# Extension.net
KiCad netlist of a schematic drawn in Altium Designer
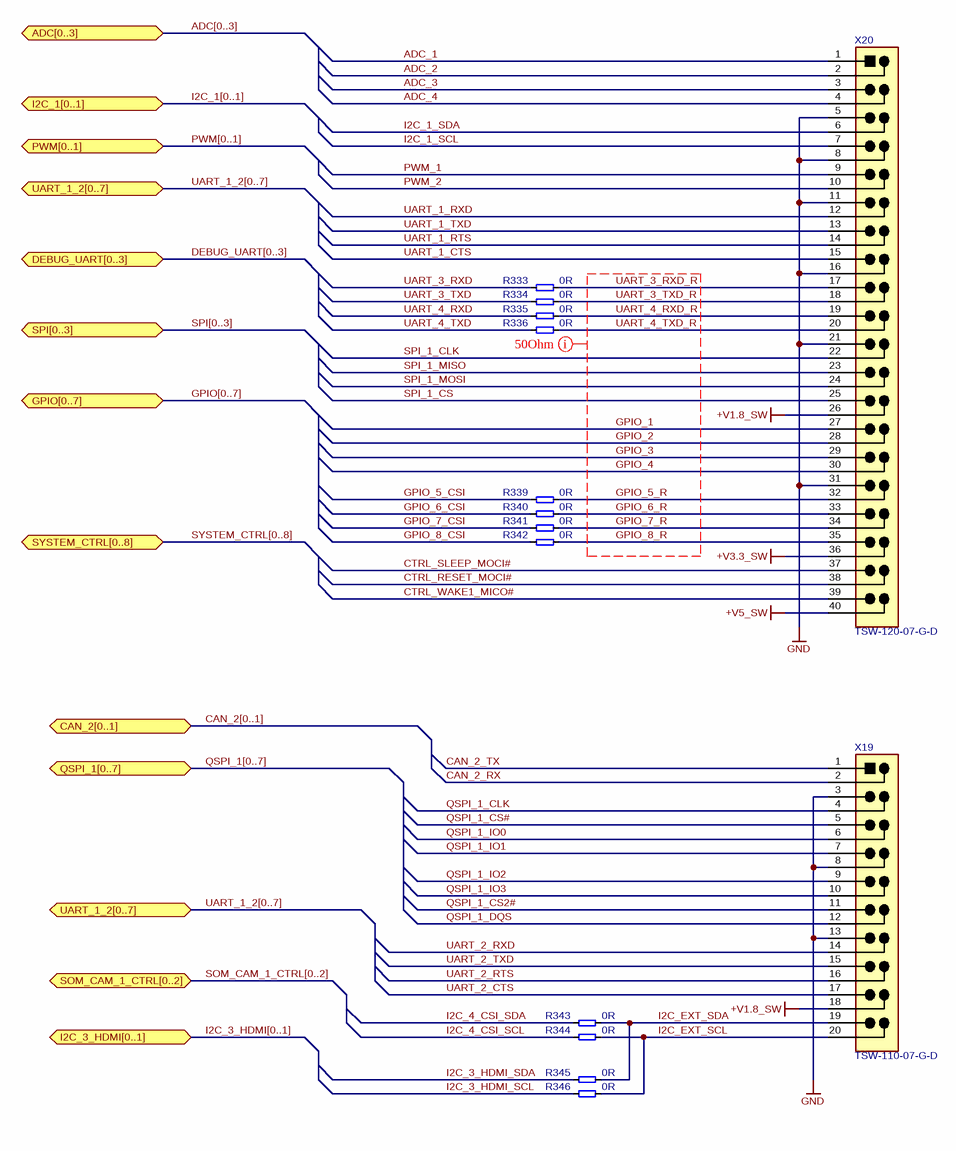
[diagram p0: Extension.SchDoc]

(export (version "E")
  (design (tool "Eeschema 10.0.6"))
  (components
    (comp (ref "R333")
      (value "0R")
      (footprint "T_RESC0603X30N")
      (description "Resistor 0 ohm 63mW 1% 0603")
      (fields (field (name "TOLERANCE") "1%"))
      (libsource (lib "Dahlia Carrier Board") (part "R-0R-63mW-1%-0603"))
    )
    (comp (ref "R334")
      (value "0R")
      (footprint "T_RESC0603X30N")
      (description "Resistor 0 ohm 63mW 1% 0603")
      (fields (field (name "TOLERANCE") "1%"))
      (libsource (lib "Dahlia Carrier Board") (part "R-0R-63mW-1%-0603"))
    )
    (comp (ref "R335")
      (value "0R")
      (footprint "T_RESC0603X30N")
      (description "Resistor 0 ohm 63mW 1% 0603")
      (fields (field (name "TOLERANCE") "1%"))
      (libsource (lib "Dahlia Carrier Board") (part "R-0R-63mW-1%-0603"))
    )
    (comp (ref "R336")
      (value "0R")
      (footprint "T_RESC0603X30N")
      (description "Resistor 0 ohm 63mW 1% 0603")
      (fields (field (name "TOLERANCE") "1%"))
      (libsource (lib "Dahlia Carrier Board") (part "R-0R-63mW-1%-0603"))
    )
    (comp (ref "R339")
      (value "0R")
      (footprint "T_RESC0603X30N")
      (description "Resistor 0 ohm 63mW 1% 0603")
      (fields (field (name "TOLERANCE") "1%"))
      (libsource (lib "Dahlia Carrier Board") (part "R-0R-63mW-1%-0603"))
    )
    (comp (ref "R340")
      (value "0R")
      (footprint "T_RESC0603X30N")
      (description "Resistor 0 ohm 63mW 1% 0603")
      (fields (field (name "TOLERANCE") "1%"))
      (libsource (lib "Dahlia Carrier Board") (part "R-0R-63mW-1%-0603"))
    )
    (comp (ref "R341")
      (value "0R")
      (footprint "T_RESC0603X30N")
      (description "Resistor 0 ohm 63mW 1% 0603")
      (fields (field (name "TOLERANCE") "1%"))
      (libsource (lib "Dahlia Carrier Board") (part "R-0R-63mW-1%-0603"))
    )
    (comp (ref "R342")
      (value "0R")
      (footprint "T_RESC0603X30N")
      (description "Resistor 0 ohm 63mW 1% 0603")
      (fields (field (name "TOLERANCE") "1%"))
      (libsource (lib "Dahlia Carrier Board") (part "R-0R-63mW-1%-0603"))
    )
    (comp (ref "R343")
      (value "0R")
      (footprint "T_RESC0603X30N")
      (description "Resistor 0 ohm 63mW 1% 0603")
      (fields (field (name "TOLERANCE") "1%"))
      (libsource (lib "Dahlia Carrier Board") (part "R-0R-63mW-1%-0603"))
    )
    (comp (ref "R344")
      (value "0R")
      (footprint "T_RESC0603X30N")
      (description "Resistor 0 ohm 63mW 1% 0603")
      (fields (field (name "TOLERANCE") "1%"))
      (libsource (lib "Dahlia Carrier Board") (part "R-0R-63mW-1%-0603"))
    )
    (comp (ref "R345")
      (value "0R")
      (footprint "T_RESC0603X30N")
      (description "Resistor 0 ohm 63mW 1% 0603")
      (fields (field (name "TOLERANCE") "1%"))
      (libsource (lib "Dahlia Carrier Board") (part "R-0R-63mW-1%-0603"))
    )
    (comp (ref "R346")
      (value "0R")
      (footprint "T_RESC0603X30N")
      (description "Resistor 0 ohm 63mW 1% 0603")
      (fields (field (name "TOLERANCE") "1%"))
      (libsource (lib "Dahlia Carrier Board") (part "R-0R-63mW-1%-0603"))
    )
    (comp (ref "X19")
      (value "TSW-110-07-G-D")
      (footprint "T_Samtec_TSW-110-07-G-D")
      (description "Header 2x10 pin 2.54mm pitch")
      (fields (field (name "MANUFACTURER PART NO.") "TSW-110-07-G-D"))
      (libsource (lib "Dahlia Carrier Board") (part "CON-Samtec-TSW-110-07-G-D"))
    )
    (comp (ref "X20")
      (value "TSW-120-07-G-D")
      (footprint "T_Samtec_TSW-120-07-G-D")
      (description "Header 2x20 pin 2.54mm pitch")
      (fields (field (name "MANUFACTURER PART NO.") "TSW-120-07-G-D"))
      (libsource (lib "Dahlia Carrier Board") (part "CON-Samtec-TSW-120-07-G-D"))
    )
  )
  (nets
    (net (code "57") (name "+V1.8_SW") (class "Default")
      (node (ref "X19") (pin "18") (pinfunction "18_18") (pintype "passive"))
      (node (ref "X20") (pin "26") (pinfunction "26_26") (pintype "passive"))
    )
    (net (code "58") (name "+V3.3_SW") (class "Default")
      (node (ref "X20") (pin "36") (pinfunction "36_36") (pintype "passive"))
    )
    (net (code "59") (name "+V5_SW") (class "Default")
      (node (ref "X20") (pin "40") (pinfunction "40_40") (pintype "passive"))
    )
    (net (code "61") (name "/ADC_1") (class "Default")
      (node (ref "X20") (pin "1") (pinfunction "1_1") (pintype "passive"))
    )
    (net (code "62") (name "/ADC_2") (class "Default")
      (node (ref "X20") (pin "2") (pinfunction "2_2") (pintype "passive"))
    )
    (net (code "63") (name "/ADC_3") (class "Default")
      (node (ref "X20") (pin "3") (pinfunction "3_3") (pintype "passive"))
    )
    (net (code "64") (name "/ADC_4") (class "Default")
      (node (ref "X20") (pin "4") (pinfunction "4_4") (pintype "passive"))
    )
    (net (code "66") (name "/CAN_2_RX") (class "Default")
      (node (ref "X19") (pin "2") (pinfunction "2_2") (pintype "passive"))
    )
    (net (code "67") (name "/CAN_2_TX") (class "Default")
      (node (ref "X19") (pin "1") (pinfunction "1_1") (pintype "passive"))
    )
    (net (code "68") (name "/CTRL_RESET_MOCI#") (class "Default")
      (node (ref "X20") (pin "38") (pinfunction "38_38") (pintype "passive"))
    )
    (net (code "69") (name "/CTRL_SLEEP_MOCI#") (class "Default")
      (node (ref "X20") (pin "37") (pinfunction "37_37") (pintype "passive"))
    )
    (net (code "70") (name "/CTRL_WAKE1_MICO#") (class "Default")
      (node (ref "X20") (pin "39") (pinfunction "39_39") (pintype "passive"))
    )
    (net (code "73") (name "/GPIO_1") (class "Default")
      (node (ref "X20") (pin "27") (pinfunction "27_27") (pintype "passive"))
    )
    (net (code "74") (name "/GPIO_2") (class "Default")
      (node (ref "X20") (pin "28") (pinfunction "28_28") (pintype "passive"))
    )
    (net (code "75") (name "/GPIO_3") (class "Default")
      (node (ref "X20") (pin "29") (pinfunction "29_29") (pintype "passive"))
    )
    (net (code "76") (name "/GPIO_4") (class "Default")
      (node (ref "X20") (pin "30") (pinfunction "30_30") (pintype "passive"))
    )
    (net (code "77") (name "/GPIO_5_CSI") (class "Default")
      (node (ref "R339") (pin "2") (pinfunction "2_2") (pintype "passive"))
    )
    (net (code "78") (name "/GPIO_5_R") (class "Default")
      (node (ref "R339") (pin "1") (pinfunction "1_1") (pintype "passive"))
      (node (ref "X20") (pin "32") (pinfunction "32_32") (pintype "passive"))
    )
    (net (code "79") (name "/GPIO_6_CSI") (class "Default")
      (node (ref "R340") (pin "2") (pinfunction "2_2") (pintype "passive"))
    )
    (net (code "80") (name "/GPIO_6_R") (class "Default")
      (node (ref "R340") (pin "1") (pinfunction "1_1") (pintype "passive"))
      (node (ref "X20") (pin "33") (pinfunction "33_33") (pintype "passive"))
    )
    (net (code "81") (name "/GPIO_7_CSI") (class "Default")
      (node (ref "R341") (pin "2") (pinfunction "2_2") (pintype "passive"))
    )
    (net (code "82") (name "/GPIO_7_R") (class "Default")
      (node (ref "R341") (pin "1") (pinfunction "1_1") (pintype "passive"))
      (node (ref "X20") (pin "34") (pinfunction "34_34") (pintype "passive"))
    )
    (net (code "83") (name "/GPIO_8_CSI") (class "Default")
      (node (ref "R342") (pin "2") (pinfunction "2_2") (pintype "passive"))
    )
    (net (code "84") (name "/GPIO_8_R") (class "Default")
      (node (ref "R342") (pin "1") (pinfunction "1_1") (pintype "passive"))
      (node (ref "X20") (pin "35") (pinfunction "35_35") (pintype "passive"))
    )
    (net (code "86") (name "/I2C_1_SCL") (class "Default")
      (node (ref "X20") (pin "7") (pinfunction "7_7") (pintype "passive"))
    )
    (net (code "87") (name "/I2C_1_SDA") (class "Default")
      (node (ref "X20") (pin "6") (pinfunction "6_6") (pintype "passive"))
    )
    (net (code "89") (name "/I2C_3_HDMI_SCL") (class "Default")
      (node (ref "R346") (pin "2") (pinfunction "2_2") (pintype "passive"))
    )
    (net (code "90") (name "/I2C_3_HDMI_SDA") (class "Default")
      (node (ref "R345") (pin "2") (pinfunction "2_2") (pintype "passive"))
    )
    (net (code "91") (name "/I2C_4_CSI_SCL") (class "Default")
      (node (ref "R344") (pin "2") (pinfunction "2_2") (pintype "passive"))
    )
    (net (code "92") (name "/I2C_4_CSI_SDA") (class "Default")
      (node (ref "R343") (pin "2") (pinfunction "2_2") (pintype "passive"))
    )
    (net (code "93") (name "/I2C_EXT_SCL") (class "Default")
      (node (ref "R344") (pin "1") (pinfunction "1_1") (pintype "passive"))
      (node (ref "R346") (pin "1") (pinfunction "1_1") (pintype "passive"))
      (node (ref "X19") (pin "20") (pinfunction "20_20") (pintype "passive"))
    )
    (net (code "94") (name "/I2C_EXT_SDA") (class "Default")
      (node (ref "R343") (pin "1") (pinfunction "1_1") (pintype "passive"))
      (node (ref "R345") (pin "1") (pinfunction "1_1") (pintype "passive"))
      (node (ref "X19") (pin "19") (pinfunction "19_19") (pintype "passive"))
    )
    (net (code "96") (name "/PWM_1") (class "Default")
      (node (ref "X20") (pin "9") (pinfunction "9_9") (pintype "passive"))
    )
    (net (code "97") (name "/PWM_2") (class "Default")
      (node (ref "X20") (pin "10") (pinfunction "10_10") (pintype "passive"))
    )
    (net (code "99") (name "/QSPI_1_CLK") (class "Default")
      (node (ref "X19") (pin "4") (pinfunction "4_4") (pintype "passive"))
    )
    (net (code "100") (name "/QSPI_1_CS#") (class "Default")
      (node (ref "X19") (pin "5") (pinfunction "5_5") (pintype "passive"))
    )
    (net (code "101") (name "/QSPI_1_CS2#") (class "Default")
      (node (ref "X19") (pin "11") (pinfunction "11_11") (pintype "passive"))
    )
    (net (code "102") (name "/QSPI_1_DQS") (class "Default")
      (node (ref "X19") (pin "12") (pinfunction "12_12") (pintype "passive"))
    )
    (net (code "103") (name "/QSPI_1_IO0") (class "Default")
      (node (ref "X19") (pin "6") (pinfunction "6_6") (pintype "passive"))
    )
    (net (code "104") (name "/QSPI_1_IO1") (class "Default")
      (node (ref "X19") (pin "7") (pinfunction "7_7") (pintype "passive"))
    )
    (net (code "105") (name "/QSPI_1_IO2") (class "Default")
      (node (ref "X19") (pin "9") (pinfunction "9_9") (pintype "passive"))
    )
    (net (code "106") (name "/QSPI_1_IO3") (class "Default")
      (node (ref "X19") (pin "10") (pinfunction "10_10") (pintype "passive"))
    )
    (net (code "109") (name "/SPI_1_CLK") (class "Default")
      (node (ref "X20") (pin "22") (pinfunction "22_22") (pintype "passive"))
    )
    (net (code "110") (name "/SPI_1_CS") (class "Default")
      (node (ref "X20") (pin "25") (pinfunction "25_25") (pintype "passive"))
    )
    (net (code "111") (name "/SPI_1_MISO") (class "Default")
      (node (ref "X20") (pin "23") (pinfunction "23_23") (pintype "passive"))
    )
    (net (code "112") (name "/SPI_1_MOSI") (class "Default")
      (node (ref "X20") (pin "24") (pinfunction "24_24") (pintype "passive"))
    )
    (net (code "115") (name "/UART_1_CTS") (class "Default")
      (node (ref "X20") (pin "15") (pinfunction "15_15") (pintype "passive"))
    )
    (net (code "116") (name "/UART_1_RTS") (class "Default")
      (node (ref "X20") (pin "14") (pinfunction "14_14") (pintype "passive"))
    )
    (net (code "117") (name "/UART_1_RXD") (class "Default")
      (node (ref "X20") (pin "12") (pinfunction "12_12") (pintype "passive"))
    )
    (net (code "118") (name "/UART_1_TXD") (class "Default")
      (node (ref "X20") (pin "13") (pinfunction "13_13") (pintype "passive"))
    )
    (net (code "119") (name "/UART_2_CTS") (class "Default")
      (node (ref "X19") (pin "17") (pinfunction "17_17") (pintype "passive"))
    )
    (net (code "120") (name "/UART_2_RTS") (class "Default")
      (node (ref "X19") (pin "16") (pinfunction "16_16") (pintype "passive"))
    )
    (net (code "121") (name "/UART_2_RXD") (class "Default")
      (node (ref "X19") (pin "14") (pinfunction "14_14") (pintype "passive"))
    )
    (net (code "122") (name "/UART_2_TXD") (class "Default")
      (node (ref "X19") (pin "15") (pinfunction "15_15") (pintype "passive"))
    )
    (net (code "123") (name "/UART_3_RXD") (class "Default")
      (node (ref "R333") (pin "2") (pinfunction "2_2") (pintype "passive"))
    )
    (net (code "124") (name "/UART_3_RXD_R") (class "Default")
      (node (ref "R333") (pin "1") (pinfunction "1_1") (pintype "passive"))
      (node (ref "X20") (pin "17") (pinfunction "17_17") (pintype "passive"))
    )
    (net (code "125") (name "/UART_3_TXD") (class "Default")
      (node (ref "R334") (pin "2") (pinfunction "2_2") (pintype "passive"))
    )
    (net (code "126") (name "/UART_3_TXD_R") (class "Default")
      (node (ref "R334") (pin "1") (pinfunction "1_1") (pintype "passive"))
      (node (ref "X20") (pin "18") (pinfunction "18_18") (pintype "passive"))
    )
    (net (code "127") (name "/UART_4_RXD") (class "Default")
      (node (ref "R335") (pin "2") (pinfunction "2_2") (pintype "passive"))
    )
    (net (code "128") (name "/UART_4_RXD_R") (class "Default")
      (node (ref "R335") (pin "1") (pinfunction "1_1") (pintype "passive"))
      (node (ref "X20") (pin "19") (pinfunction "19_19") (pintype "passive"))
    )
    (net (code "129") (name "/UART_4_TXD") (class "Default")
      (node (ref "R336") (pin "2") (pinfunction "2_2") (pintype "passive"))
    )
    (net (code "130") (name "/UART_4_TXD_R") (class "Default")
      (node (ref "R336") (pin "1") (pinfunction "1_1") (pintype "passive"))
      (node (ref "X20") (pin "20") (pinfunction "20_20") (pintype "passive"))
    )
    (net (code "131") (name "GND") (class "Default")
      (node (ref "X19") (pin "13") (pinfunction "13_13") (pintype "passive"))
      (node (ref "X19") (pin "3") (pinfunction "3_3") (pintype "passive"))
      (node (ref "X19") (pin "8") (pinfunction "8_8") (pintype "passive"))
      (node (ref "X20") (pin "11") (pinfunction "11_11") (pintype "passive"))
      (node (ref "X20") (pin "16") (pinfunction "16_16") (pintype "passive"))
      (node (ref "X20") (pin "21") (pinfunction "21_21") (pintype "passive"))
      (node (ref "X20") (pin "31") (pinfunction "31_31") (pintype "passive"))
      (node (ref "X20") (pin "5") (pinfunction "5_5") (pintype "passive"))
      (node (ref "X20") (pin "8") (pinfunction "8_8") (pintype "passive"))
    )
  )
)
